# ports.net
KiCad netlist of a schematic drawn in Altium Designer
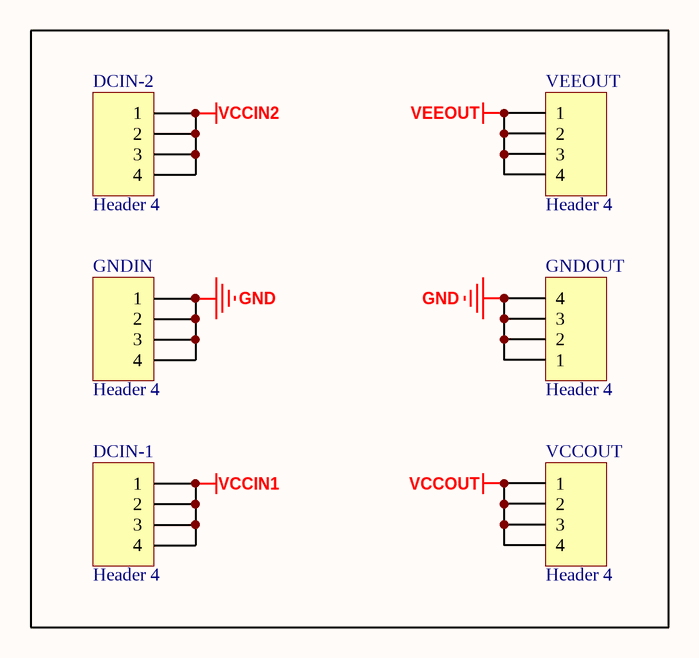
[diagram p0: ports.SchDoc]

(export (version "E")
  (design (tool "Eeschema 10.0.6"))
  (components
    (comp (ref "DCIN-1")
      (value "Header 4")
      (footprint "HDR1X4")
      (description "Header, 4-Pin")
      (fields (field (name "PUBLISHER") "Altium Limited"))
      (libsource (lib "xz_C") (part "Header 4"))
    )
    (comp (ref "DCIN-2")
      (value "Header 4")
      (footprint "HDR1X4")
      (description "Header, 4-Pin")
      (fields (field (name "PUBLISHER") "Altium Limited"))
      (libsource (lib "xz_C") (part "Header 4"))
    )
    (comp (ref "GNDIN")
      (value "Header 4")
      (footprint "HDR1X4")
      (description "Header, 4-Pin")
      (fields (field (name "PUBLISHER") "Altium Limited"))
      (libsource (lib "xz_C") (part "Header 4"))
    )
    (comp (ref "GNDOUT")
      (value "Header 4")
      (footprint "HDR1X4")
      (description "Header, 4-Pin")
      (fields (field (name "PUBLISHER") "Altium Limited"))
      (libsource (lib "") (part "Header 4_2"))
    )
    (comp (ref "VCCOUT")
      (value "Header 4")
      (footprint "HDR1X4")
      (description "Header, 4-Pin")
      (fields (field (name "PUBLISHER") "Altium Limited"))
      (libsource (lib "") (part "Header 4_1"))
    )
    (comp (ref "VEEOUT")
      (value "Header 4")
      (footprint "HDR1X4")
      (description "Header, 4-Pin")
      (fields (field (name "PUBLISHER") "Altium Limited"))
      (libsource (lib "") (part "Header 4_1"))
    )
  )
  (nets
    (net (code "1") (name "GND") (class "Default")
      (node (ref "GNDIN") (pin "1") (pinfunction "1_1") (pintype "passive"))
      (node (ref "GNDIN") (pin "2") (pinfunction "2_2") (pintype "passive"))
      (node (ref "GNDIN") (pin "3") (pinfunction "3_3") (pintype "passive"))
      (node (ref "GNDIN") (pin "4") (pinfunction "4_4") (pintype "passive"))
      (node (ref "GNDOUT") (pin "1") (pinfunction "1_1") (pintype "passive"))
      (node (ref "GNDOUT") (pin "2") (pinfunction "2_2") (pintype "passive"))
      (node (ref "GNDOUT") (pin "3") (pinfunction "3_3") (pintype "passive"))
      (node (ref "GNDOUT") (pin "4") (pinfunction "4_4") (pintype "passive"))
    )
    (net (code "2") (name "VCCIN1") (class "Default")
      (node (ref "DCIN-1") (pin "1") (pinfunction "1_1") (pintype "passive"))
      (node (ref "DCIN-1") (pin "2") (pinfunction "2_2") (pintype "passive"))
      (node (ref "DCIN-1") (pin "3") (pinfunction "3_3") (pintype "passive"))
      (node (ref "DCIN-1") (pin "4") (pinfunction "4_4") (pintype "passive"))
    )
    (net (code "3") (name "VCCIN2") (class "Default")
      (node (ref "DCIN-2") (pin "1") (pinfunction "1_1") (pintype "passive"))
      (node (ref "DCIN-2") (pin "2") (pinfunction "2_2") (pintype "passive"))
      (node (ref "DCIN-2") (pin "3") (pinfunction "3_3") (pintype "passive"))
      (node (ref "DCIN-2") (pin "4") (pinfunction "4_4") (pintype "passive"))
    )
    (net (code "4") (name "VCCOUT") (class "Default")
      (node (ref "VCCOUT") (pin "1") (pinfunction "1_1") (pintype "passive"))
      (node (ref "VCCOUT") (pin "2") (pinfunction "2_2") (pintype "passive"))
      (node (ref "VCCOUT") (pin "3") (pinfunction "3_3") (pintype "passive"))
      (node (ref "VCCOUT") (pin "4") (pinfunction "4_4") (pintype "passive"))
    )
    (net (code "5") (name "VEEOUT") (class "Default")
      (node (ref "VEEOUT") (pin "1") (pinfunction "1_1") (pintype "passive"))
      (node (ref "VEEOUT") (pin "2") (pinfunction "2_2") (pintype "passive"))
      (node (ref "VEEOUT") (pin "3") (pinfunction "3_3") (pintype "passive"))
      (node (ref "VEEOUT") (pin "4") (pinfunction "4_4") (pintype "passive"))
    )
  )
)
